# 05_Analog.net
KiCad netlist of a schematic drawn in Altium Designer
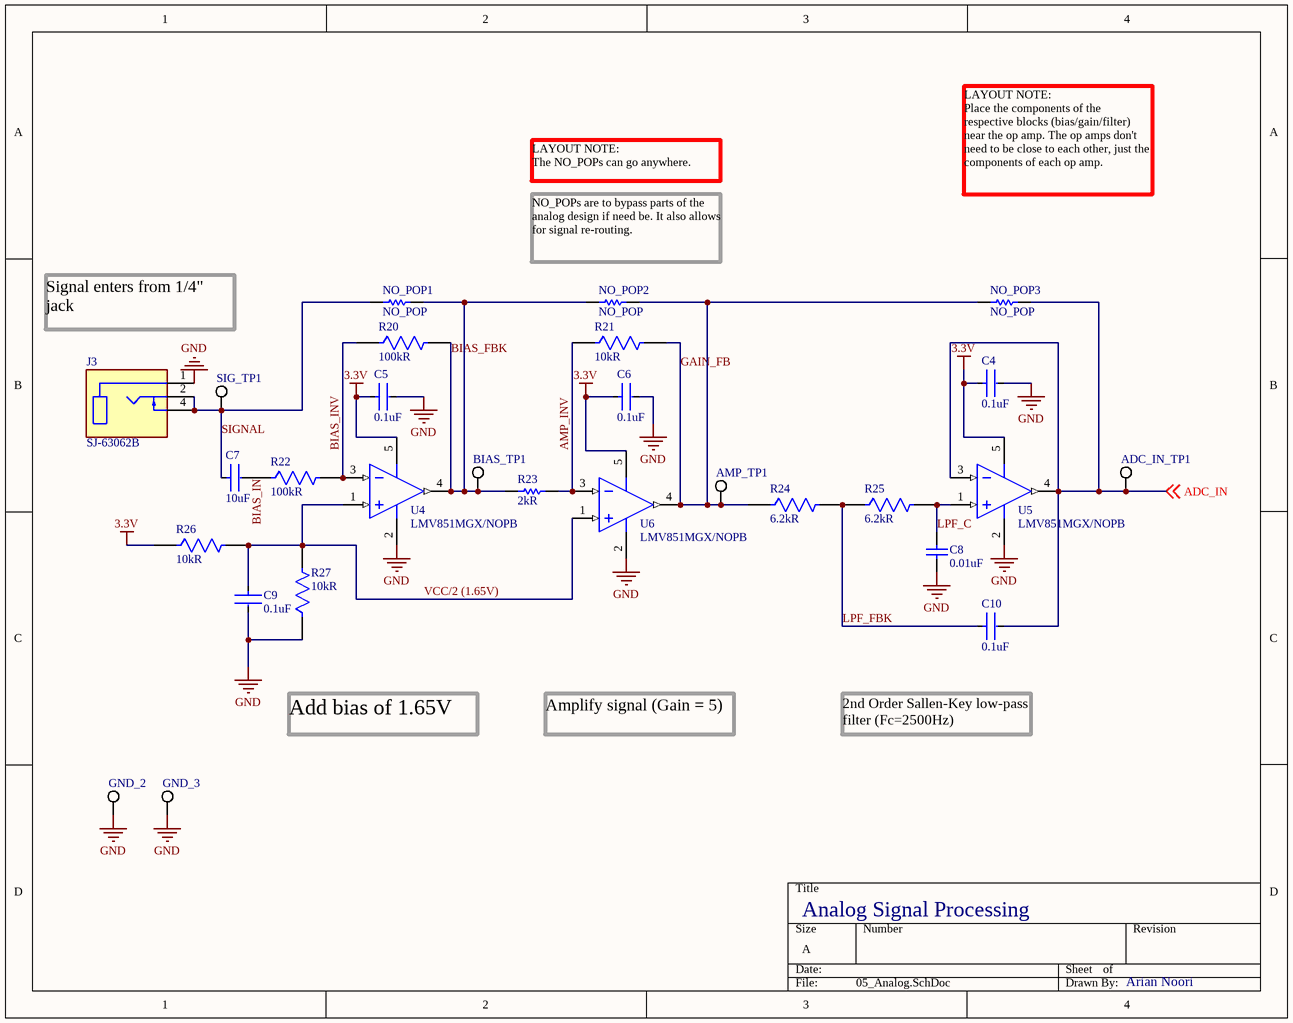
[diagram p0: 05_Analog.SchDoc]

(export (version "E")
  (design (tool "Eeschema 10.0.6"))
  (components
    (comp (ref "ADC_IN_TP1")
      (value "5019")
      (footprint "KSTN-5019_V")
      (description "Test Point, 1 Position SMD, RoHS, Tape and Reel")
      (fields (field (name "MANUFACTURER") "Keystone Electronics"))
      (libsource (lib "Altium Content Vault") (part "TESTPOINT_WHITE"))
    )
    (comp (ref "AMP_TP1")
      (value "5019")
      (footprint "KSTN-5019_V")
      (description "Test Point, 1 Position SMD, RoHS, Tape and Reel")
      (fields (field (name "MANUFACTURER") "Keystone Electronics"))
      (libsource (lib "Altium Content Vault") (part "TESTPOINT_WHITE"))
    )
    (comp (ref "BIAS_TP1")
      (value "5019")
      (footprint "KSTN-5019_V")
      (description "Test Point, 1 Position SMD, RoHS, Tape and Reel")
      (fields (field (name "MANUFACTURER") "Keystone Electronics"))
      (libsource (lib "Altium Content Vault") (part "TESTPOINT_WHITE"))
    )
    (comp (ref "C4")
      (value "0.1uF")
      (footprint "FP-CL21-IPC_C")
      (description "CL21 Series 0805 100nF 50V ±10% Tolerance X7R Multilayer Ceramic Chip Capacitor")
      (fields (field (name "TOLERANCE") "10%") (field (name "VOLTAGE") "50V"))
      (libsource (lib "Altium Content Vault") (part "b4654b650e69147ec39a6b967a45e02"))
    )
    (comp (ref "C5")
      (value "0.1uF")
      (footprint "FP-CL21-IPC_C")
      (description "CL21 Series 0805 100nF 50V ±10% Tolerance X7R Multilayer Ceramic Chip Capacitor")
      (fields (field (name "TOLERANCE") "10%") (field (name "VOLTAGE") "50V"))
      (libsource (lib "Altium Content Vault") (part "b4654b650e69147ec39a6b967a45e02"))
    )
    (comp (ref "C6")
      (value "0.1uF")
      (footprint "FP-CL21-IPC_C")
      (description "CL21 Series 0805 100nF 50V ±10% Tolerance X7R Multilayer Ceramic Chip Capacitor")
      (fields (field (name "TOLERANCE") "10%") (field (name "VOLTAGE") "50V"))
      (libsource (lib "Altium Content Vault") (part "b4654b650e69147ec39a6b967a45e02"))
    )
    (comp (ref "C7")
      (value "10uF")
      (footprint "FP-CL21-IPC_B")
      (description "CL21 Series 0805 10uF 10V ±10% Tolerance X5R Multilayer Ceramic Chip Capacitor")
      (fields (field (name "TOLERANCE") "10%") (field (name "MANUFACTURER") "Samsung"))
      (libsource (lib "Altium Content Vault") (part "b4654b650e69147ec39a6b967a45e02"))
    )
    (comp (ref "C8")
      (value "0.01uF")
      (footprint "CAPC2013X75X45LL10T25")
      (description "Multilayer Ceramic Capacitor, 10 nF, 50 V, -55 to 125 degC, 2-Pin SMD, RoHS, Tape and Reel")
      (fields
        (field (name "MANUFACTURER") "Samsung Electro-Mechanics")
        (field (name "MANUFACTURER PART NUMBER") "CL21B103KBANNNC")
      )
      (libsource (lib "Altium Content Vault") (part "CAP-NP-2"))
    )
    (comp (ref "C9")
      (value "0.1uF")
      (footprint "FP-CL21-IPC_C")
      (description "CL21 Series 0805 100nF 50V ±10% Tolerance X7R Multilayer Ceramic Chip Capacitor")
      (fields (field (name "TOLERANCE") "10%") (field (name "VOLTAGE") "50V"))
      (libsource (lib "Altium Content Vault") (part "b4654b650e69147ec39a6b967a45e02"))
    )
    (comp (ref "C10")
      (value "0.1uF")
      (footprint "FP-CL21-IPC_C")
      (description "CL21 Series 0805 100nF 50V ±10% Tolerance X7R Multilayer Ceramic Chip Capacitor")
      (fields (field (name "TOLERANCE") "10%") (field (name "VOLTAGE") "50V"))
      (libsource (lib "Altium Content Vault") (part "b4654b650e69147ec39a6b967a45e02"))
    )
    (comp (ref "GND_2")
      (value "5019")
      (footprint "KSTN-5019_V")
      (description "Test Point, 1 Position SMD, RoHS, Tape and Reel")
      (fields (field (name "MANUFACTURER") "Keystone Electronics"))
      (libsource (lib "Altium Content Vault") (part "TESTPOINT_WHITE"))
    )
    (comp (ref "GND_3")
      (value "5019")
      (footprint "KSTN-5019_V")
      (description "Test Point, 1 Position SMD, RoHS, Tape and Reel")
      (fields (field (name "MANUFACTURER") "Keystone Electronics"))
      (libsource (lib "Altium Content Vault") (part "TESTPOINT_WHITE"))
    )
    (comp (ref "J3")
      (value "SJ-63062B")
      (footprint "CUI_SJ-63062B")
      (fields (field (name "MANUFACTURER") "CUI Devices"))
      (libsource (lib "SJ-63062B") (part "SJ-63062B"))
    )
    (comp (ref "NO_POP1")
      (value "NO_POP")
      (footprint "RESC2013X60X35ML10T20")
      (fields
        (field (name "TOLERANCE") "5%")
        (field (name "MANUFACTURER") "Yageo")
        (field (name "MANUFACTURER PART NUMBER") "RC0805JR-070RL")
      )
      (libsource (lib "Altium Content Vault") (part "RES-2"))
    )
    (comp (ref "NO_POP2")
      (value "NO_POP")
      (footprint "RESC2013X60X35ML10T20")
      (fields
        (field (name "TOLERANCE") "5%")
        (field (name "MANUFACTURER") "Yageo")
        (field (name "MANUFACTURER PART NUMBER") "RC0805JR-070RL")
      )
      (libsource (lib "Altium Content Vault") (part "RES-2"))
    )
    (comp (ref "NO_POP3")
      (value "NO_POP")
      (footprint "RESC2013X60X35ML10T20")
      (fields
        (field (name "TOLERANCE") "5%")
        (field (name "MANUFACTURER") "Yageo")
        (field (name "MANUFACTURER PART NUMBER") "RC0805JR-070RL")
      )
      (libsource (lib "Altium Content Vault") (part "RES-2"))
    )
    (comp (ref "R20")
      (value "100kR")
      (footprint "FP-RT0805-MFG")
      (description "RES 100K OHM 1/8W .5% SMD 0805")
      (fields
        (field (name "MANUFACTURER PART NUMBER") "RT0805DRE07100KL")
        (field (name "OCTOPART") "https://octopart.com/rt0805dre07100kl-yageo-1433075")
      )
      (libsource (lib "Altium Content Vault") (part "1029c3af85768c4190bb7ad29bc67b5"))
    )
    (comp (ref "R21")
      (value "10kR")
      (footprint "FP-RT0805-MFG")
      (description "RES 10.0K OHM 1/8W .5% SMD 0805")
      (fields
        (field (name "MANUFACTURER") "Yageo")
        (field (name "MANUFACTURER PART NUMBER") "RT0805DRE0710KL")
      )
      (libsource (lib "Altium Content Vault") (part "1029c3af85768c4190bb7ad29bc67b5"))
    )
    (comp (ref "R22")
      (value "100kR")
      (footprint "FP-RT0805-MFG")
      (description "RES 100K OHM 1/8W .5% SMD 0805")
      (fields
        (field (name "MANUFACTURER PART NUMBER") "RT0805DRE07100KL")
        (field (name "OCTOPART") "https://octopart.com/rt0805dre07100kl-yageo-1433075")
      )
      (libsource (lib "Altium Content Vault") (part "1029c3af85768c4190bb7ad29bc67b5"))
    )
    (comp (ref "R23")
      (value "2kR")
      (footprint "RESC2013X60X35LL10T20")
      (description "RES 2K OHM 1/8W .5% SMD 0805")
      (fields (field (name "PART NUMBER") "RT0805FRE072KL") (field (name "MANUFACTURER") "Yageo"))
      (libsource (lib "Altium Content Vault") (part "RES"))
    )
    (comp (ref "R24")
      (value "6.2kR")
      (footprint "FP-RT0805-MFG")
      (description "RES SMD 6.2K OHM 1% 1/8W 0805")
      (fields (field (name "TOLERANCE") "0.0001") (field (name "MANUFACTURER PART NUMBER") "RT0805FRE076K2L"))
      (libsource (lib "Altium Content Vault") (part "1029c3af85768c4190bb7ad29bc67b5"))
    )
    (comp (ref "R25")
      (value "6.2kR")
      (footprint "FP-RT0805-MFG")
      (description "RES SMD 6.2K OHM 1% 1/8W 0805")
      (fields (field (name "TOLERANCE") "0.0001") (field (name "MANUFACTURER PART NUMBER") "RT0805FRE076K2L"))
      (libsource (lib "Altium Content Vault") (part "1029c3af85768c4190bb7ad29bc67b5"))
    )
    (comp (ref "R26")
      (value "10kR")
      (footprint "FP-RT0805-MFG")
      (description "RES 10.0K OHM 1/8W .5% SMD 0805")
      (fields
        (field (name "MANUFACTURER") "Yageo")
        (field (name "MANUFACTURER PART NUMBER") "RT0805DRE0710KL")
      )
      (libsource (lib "Altium Content Vault") (part "1029c3af85768c4190bb7ad29bc67b5"))
    )
    (comp (ref "R27")
      (value "10kR")
      (footprint "FP-RT0805-MFG")
      (description "RES 10.0K OHM 1/8W .5% SMD 0805")
      (fields
        (field (name "MANUFACTURER") "Yageo")
        (field (name "MANUFACTURER PART NUMBER") "RT0805DRE0710KL")
      )
      (libsource (lib "Altium Content Vault") (part "1029c3af85768c4190bb7ad29bc67b5"))
    )
    (comp (ref "SIG_TP1")
      (value "5019")
      (footprint "KSTN-5019_V")
      (description "Test Point, 1 Position SMD, RoHS, Tape and Reel")
      (fields (field (name "MANUFACTURER") "Keystone Electronics"))
      (libsource (lib "Altium Content Vault") (part "TESTPOINT_WHITE"))
    )
    (comp (ref "U4")
      (value "LMV851MGX/NOPB")
      (footprint "DCK0005A_N")
      (description "Single 8 MHz Low Power CMOS, EMI Hardened Operational Amplifier, 5-pin SC-70, Pb-Free")
      (fields (field (name "MANUFACTURER") "Texas Instruments"))
      (libsource (lib "Altium Content Vault") (part "AMP-OPA-LMV551-5"))
    )
    (comp (ref "U5")
      (value "LMV851MGX/NOPB")
      (footprint "DCK0005A_N")
      (description "Single 8 MHz Low Power CMOS, EMI Hardened Operational Amplifier, 5-pin SC-70, Pb-Free")
      (fields (field (name "MANUFACTURER") "Texas Instruments"))
      (libsource (lib "Altium Content Vault") (part "AMP-OPA-LMV551-5"))
    )
    (comp (ref "U6")
      (value "LMV851MGX/NOPB")
      (footprint "DCK0005A_N")
      (description "Single 8 MHz Low Power CMOS, EMI Hardened Operational Amplifier, 5-pin SC-70, Pb-Free")
      (fields (field (name "MANUFACTURER") "Texas Instruments"))
      (libsource (lib "Altium Content Vault") (part "AMP-OPA-LMV551-5"))
    )
  )
  (nets
    (net (code "1") (name "/AMP_INV") (class "Default")
      (node (ref "R21") (pin "1") (pinfunction "1_1") (pintype "passive"))
      (node (ref "R23") (pin "2") (pinfunction "2_2") (pintype "passive"))
      (node (ref "U6") (pin "3") (pinfunction "IN-_3") (pintype "input"))
    )
    (net (code "2") (name "/BIAS_FBK") (class "Default")
      (node (ref "BIAS_TP1") (pin "1") (pinfunction "1_1") (pintype "passive"))
      (node (ref "NO_POP1") (pin "2") (pinfunction "2_2") (pintype "passive"))
      (node (ref "NO_POP2") (pin "1") (pinfunction "1_1") (pintype "passive"))
      (node (ref "R20") (pin "2") (pinfunction "2_2") (pintype "passive"))
      (node (ref "R23") (pin "1") (pinfunction "1_1") (pintype "passive"))
      (node (ref "U4") (pin "4") (pinfunction "OUT_4") (pintype "output"))
    )
    (net (code "3") (name "/BIAS_IN") (class "Default")
      (node (ref "C7") (pin "2") (pinfunction "2_2") (pintype "passive"))
      (node (ref "R22") (pin "1") (pinfunction "1_1") (pintype "passive"))
    )
    (net (code "4") (name "/BIAS_INV") (class "Default")
      (node (ref "R20") (pin "1") (pinfunction "1_1") (pintype "passive"))
      (node (ref "R22") (pin "2") (pinfunction "2_2") (pintype "passive"))
      (node (ref "U4") (pin "3") (pinfunction "IN-_3") (pintype "input"))
    )
    (net (code "5") (name "/GAIN_FB") (class "Default")
      (node (ref "AMP_TP1") (pin "1") (pinfunction "1_1") (pintype "passive"))
      (node (ref "NO_POP2") (pin "2") (pinfunction "2_2") (pintype "passive"))
      (node (ref "NO_POP3") (pin "1") (pinfunction "1_1") (pintype "passive"))
      (node (ref "R21") (pin "2") (pinfunction "2_2") (pintype "passive"))
      (node (ref "R24") (pin "1") (pinfunction "1_1") (pintype "passive"))
      (node (ref "U6") (pin "4") (pinfunction "OUT_4") (pintype "output"))
    )
    (net (code "6") (name "/LPF_C") (class "Default")
      (node (ref "C8") (pin "1") (pinfunction "1_1") (pintype "passive"))
      (node (ref "R25") (pin "2") (pinfunction "2_2") (pintype "passive"))
      (node (ref "U5") (pin "1") (pinfunction "IN+_1") (pintype "input"))
    )
    (net (code "7") (name "/LPF_FBK") (class "Default")
      (node (ref "C10") (pin "1") (pinfunction "1_1") (pintype "passive"))
      (node (ref "R24") (pin "2") (pinfunction "2_2") (pintype "passive"))
      (node (ref "R25") (pin "1") (pinfunction "1_1") (pintype "passive"))
    )
    (net (code "8") (name "/SIGNAL") (class "Default")
      (node (ref "C7") (pin "1") (pinfunction "1_1") (pintype "passive"))
      (node (ref "J3") (pin "2") (pinfunction "TIP_2") (pintype "passive"))
      (node (ref "J3") (pin "4") (pinfunction "TIP_SWITCH_4") (pintype "passive"))
      (node (ref "NO_POP1") (pin "1") (pinfunction "1_1") (pintype "passive"))
      (node (ref "SIG_TP1") (pin "1") (pinfunction "1_1") (pintype "passive"))
    )
    (net (code "9") (name "/VCC{slash}2 (1.65V)") (class "Default")
      (node (ref "C9") (pin "1") (pinfunction "1_1") (pintype "passive"))
      (node (ref "R26") (pin "2") (pinfunction "2_2") (pintype "passive"))
      (node (ref "R27") (pin "2") (pinfunction "2_2") (pintype "passive"))
      (node (ref "U4") (pin "1") (pinfunction "IN+_1") (pintype "input"))
      (node (ref "U6") (pin "1") (pinfunction "IN+_1") (pintype "input"))
    )
    (net (code "10") (name "3.3V") (class "Default")
      (node (ref "C4") (pin "1") (pinfunction "1_1") (pintype "passive"))
      (node (ref "C5") (pin "1") (pinfunction "1_1") (pintype "passive"))
      (node (ref "C6") (pin "1") (pinfunction "1_1") (pintype "passive"))
      (node (ref "R26") (pin "1") (pinfunction "1_1") (pintype "passive"))
      (node (ref "U4") (pin "5") (pinfunction "V+_5") (pintype "power_in"))
      (node (ref "U5") (pin "5") (pinfunction "V+_5") (pintype "power_in"))
      (node (ref "U6") (pin "5") (pinfunction "V+_5") (pintype "power_in"))
    )
    (net (code "11") (name "ADC_IN") (class "Default")
      (node (ref "ADC_IN_TP1") (pin "1") (pinfunction "1_1") (pintype "passive"))
      (node (ref "C10") (pin "2") (pinfunction "2_2") (pintype "passive"))
      (node (ref "NO_POP3") (pin "2") (pinfunction "2_2") (pintype "passive"))
      (node (ref "U5") (pin "3") (pinfunction "IN-_3") (pintype "input"))
      (node (ref "U5") (pin "4") (pinfunction "OUT_4") (pintype "output"))
    )
    (net (code "12") (name "GND") (class "Default")
      (node (ref "C4") (pin "2") (pinfunction "2_2") (pintype "passive"))
      (node (ref "C5") (pin "2") (pinfunction "2_2") (pintype "passive"))
      (node (ref "C6") (pin "2") (pinfunction "2_2") (pintype "passive"))
      (node (ref "C8") (pin "2") (pinfunction "2_2") (pintype "passive"))
      (node (ref "C9") (pin "2") (pinfunction "2_2") (pintype "passive"))
      (node (ref "GND_2") (pin "1") (pinfunction "1_1") (pintype "passive"))
      (node (ref "GND_3") (pin "1") (pinfunction "1_1") (pintype "passive"))
      (node (ref "J3") (pin "1") (pinfunction "SLEEVE_1") (pintype "passive"))
      (node (ref "R27") (pin "1") (pinfunction "1_1") (pintype "passive"))
      (node (ref "U4") (pin "2") (pinfunction "V-_2") (pintype "power_in"))
      (node (ref "U5") (pin "2") (pinfunction "V-_2") (pintype "power_in"))
      (node (ref "U6") (pin "2") (pinfunction "V-_2") (pintype "power_in"))
    )
  )
)
